# Potentiometer_breakout_module.net
KiCad netlist of a schematic drawn in Altium Designer
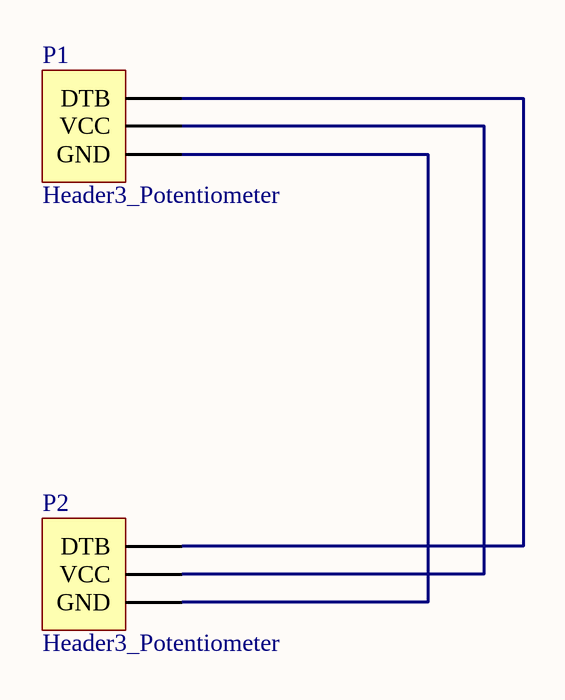
[diagram p0: Potentiometer_breakout_module.SchDoc]

(export (version "E")
  (design (tool "Eeschema 10.0.6"))
  (components
    (comp (ref "P1")
      (value "Header3_Potentiometer")
      (footprint "HDR1X3_Potentiometer")
      (libsource (lib "Schlib2") (part "Header3_Potentiometer"))
    )
    (comp (ref "P2")
      (value "Header3_Potentiometer")
      (footprint "HDR1X3_Potentiometer")
      (libsource (lib "Schlib2") (part "Header3_Potentiometer"))
    )
  )
  (nets
    (net (code "1") (name "Net-(P1-DTB)") (class "Default")
      (node (ref "P1") (pin "3") (pinfunction "DTB_3") (pintype "passive"))
      (node (ref "P2") (pin "3") (pinfunction "DTB_3") (pintype "passive"))
    )
    (net (code "2") (name "Net-(P1-GND)") (class "Default")
      (node (ref "P1") (pin "1") (pinfunction "GND_1") (pintype "passive"))
      (node (ref "P2") (pin "1") (pinfunction "GND_1") (pintype "passive"))
    )
    (net (code "3") (name "Net-(P1-VCC)") (class "Default")
      (node (ref "P1") (pin "2") (pinfunction "VCC_2") (pintype "passive"))
      (node (ref "P2") (pin "2") (pinfunction "VCC_2") (pintype "passive"))
    )
  )
)
